# 2012_FDP_Generic_Port_Act.net
KiCad netlist of a schematic drawn in Altium Designer
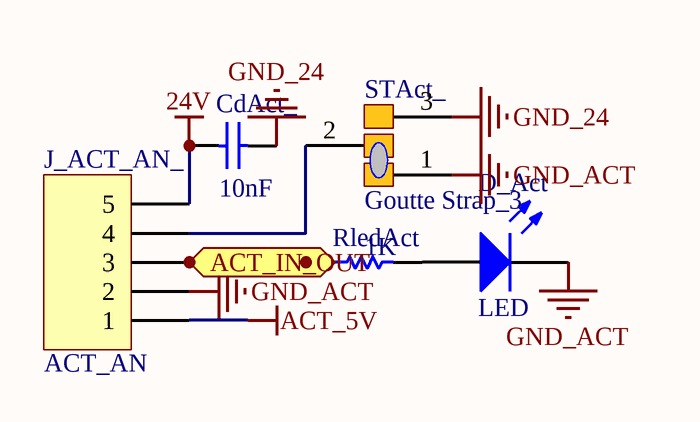
[diagram p0: 2012_FDP_Generic_Port_Act.SchDoc]

(export (version "E")
  (design (tool "Eeschema 10.0.6"))
  (components
    (comp (ref "CdAct_")
      (value "10nF")
      (footprint "C0805_N")
      (description "Capacitor")
      (fields (field (name "PUBLISHER") "Altium Limited"))
      (libsource (lib "_ROBOT") (part "Condensateur"))
    )
    (comp (ref "D_Act")
      (value "LED")
      (footprint "LED_0805")
      (description "Typical LED")
      (fields (field (name "PUBLISHER") "Altium Limited"))
      (libsource (lib "_ROBOT") (part "LED"))
    )
    (comp (ref "J_ACT_AN_")
      (value "ACT_AN")
      (footprint "HE14_5")
      (description "Header, 5-Pin")
      (fields (field (name "PUBLISHER") "Altium Limited"))
      (libsource (lib "Connecteur") (part "BARRETTE5"))
    )
    (comp (ref "RledAct")
      (value "1K")
      (footprint "R1206_N")
      (description "Resistor")
      (fields (field (name "PUBLISHER") "Altium Limited"))
      (libsource (lib "_ROBOT") (part "Resistor"))
    )
    (comp (ref "STAct_")
      (value "Goutte Strap_3")
      (footprint "Goutte Strap_3")
      (fields (field (name "PUBLISHER") "Damien Guitton"))
      (libsource (lib "DG_Connecteur") (part "Goutte Strap_3"))
    )
  )
  (nets
    (net (code "1") (name "/ACT_IN_OUT") (class "Default")
      (node (ref "J_ACT_AN_") (pin "3") (pinfunction "3_3") (pintype "passive"))
      (node (ref "RledAct") (pin "1") (pinfunction "1_1") (pintype "passive"))
    )
    (net (code "2") (name "24V") (class "Default")
      (node (ref "CdAct_") (pin "1") (pinfunction "1_1") (pintype "passive"))
      (node (ref "J_ACT_AN_") (pin "5") (pinfunction "5_5") (pintype "passive"))
    )
    (net (code "3") (name "ACT_5V") (class "Default")
      (node (ref "J_ACT_AN_") (pin "1") (pinfunction "1_1") (pintype "passive"))
    )
    (net (code "4") (name "GND_24") (class "Default")
      (node (ref "CdAct_") (pin "2") (pinfunction "2_2") (pintype "passive"))
      (node (ref "STAct_") (pin "3") (pinfunction "3_3") (pintype "passive"))
    )
    (net (code "5") (name "GND_ACT") (class "Default")
      (node (ref "D_Act") (pin "2") (pinfunction "K_2") (pintype "passive"))
      (node (ref "J_ACT_AN_") (pin "2") (pinfunction "2_2") (pintype "passive"))
      (node (ref "STAct_") (pin "1") (pinfunction "1_1") (pintype "passive"))
    )
    (net (code "6") (name "Net-(D_Act-A)") (class "Default")
      (node (ref "D_Act") (pin "1") (pinfunction "A_1") (pintype "passive"))
      (node (ref "RledAct") (pin "2") (pinfunction "2_2") (pintype "passive"))
    )
    (net (code "7") (name "Net-(J_ACT_AN_-Pad4)") (class "Default")
      (node (ref "J_ACT_AN_") (pin "4") (pinfunction "4_4") (pintype "passive"))
      (node (ref "STAct_") (pin "2") (pinfunction "2_2") (pintype "passive"))
    )
  )
)
